# CristmasVillage_Driver_1-3.net
KiCad netlist of a schematic drawn in EAGLE
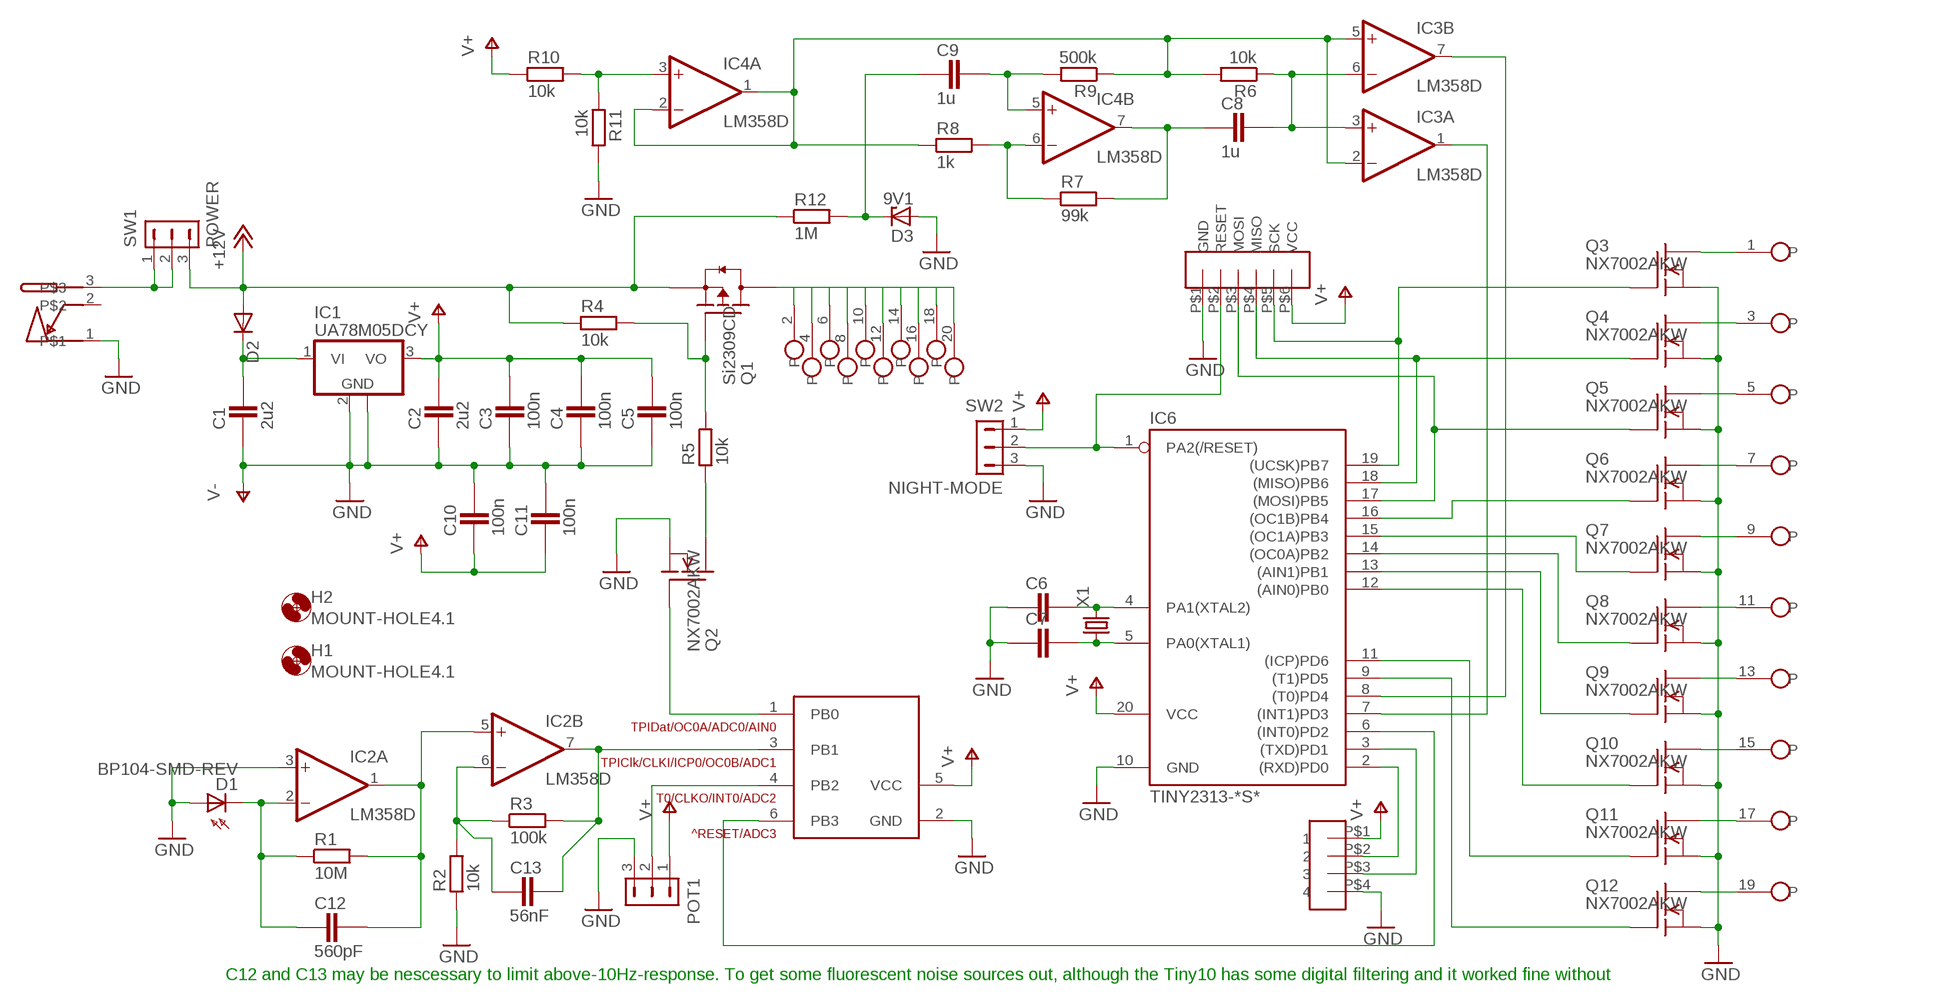
[diagram p0: schematic, sheet 1]

(export (version "E")
  (design (tool "Eeschema 10.0.6"))
  (components
    (comp (ref "C1")
      (value "2u2")
      (footprint "eagle-import:CAPC3215X168N")
      (libsource (lib "eagle-import") (part "CAPACITOR_1206"))
    )
    (comp (ref "C2")
      (value "2u2")
      (footprint "eagle-import:CAPC3215X168N")
      (libsource (lib "eagle-import") (part "CAPACITOR_1206"))
    )
    (comp (ref "C3")
      (value "100n")
      (footprint "eagle-import:CAPC1608X92N")
      (libsource (lib "eagle-import") (part "CAPACITOR_0603"))
    )
    (comp (ref "C4")
      (value "100n")
      (footprint "eagle-import:CAPC1608X92N")
      (libsource (lib "eagle-import") (part "CAPACITOR_0603"))
    )
    (comp (ref "C5")
      (value "100n")
      (footprint "eagle-import:CAPC1608X92N")
      (libsource (lib "eagle-import") (part "CAPACITOR_0603"))
    )
    (comp (ref "C6")
      (value "CAPACITOR_0603")
      (footprint "eagle-import:CAPC1608X92N")
      (libsource (lib "eagle-import") (part "CAPACITOR_0603"))
    )
    (comp (ref "C7")
      (value "CAPACITOR_0603")
      (footprint "eagle-import:CAPC1608X92N")
      (libsource (lib "eagle-import") (part "CAPACITOR_0603"))
    )
    (comp (ref "C8")
      (value "1u")
      (footprint "eagle-import:CAPC3215X168N")
      (libsource (lib "eagle-import") (part "CAPACITOR_1206"))
    )
    (comp (ref "C9")
      (value "1u")
      (footprint "eagle-import:CAPC3215X168N")
      (libsource (lib "eagle-import") (part "CAPACITOR_1206"))
    )
    (comp (ref "C10")
      (value "100n")
      (footprint "eagle-import:CAPC1608X92N")
      (libsource (lib "eagle-import") (part "CAPACITOR_0603"))
    )
    (comp (ref "C11")
      (value "100n")
      (footprint "eagle-import:CAPC1608X92N")
      (libsource (lib "eagle-import") (part "CAPACITOR_0603"))
    )
    (comp (ref "C12")
      (value "560pF")
      (footprint "eagle-import:CAPC1608X92N")
      (libsource (lib "eagle-import") (part "CAPACITOR_0603"))
    )
    (comp (ref "C13")
      (value "56nF")
      (footprint "eagle-import:CAPC1608X92N")
      (libsource (lib "eagle-import") (part "CAPACITOR_0603"))
    )
    (comp (ref "CN1")
      (value "MJ-180SMT")
      (footprint "eagle-import:MJ-180SMT")
      (libsource (lib "eagle-import") (part "MJ-180SMT"))
    )
    (comp (ref "CN2-PROG")
      (value "JST-6PSPI-SIDE-S6B")
      (footprint "eagle-import:6P-H")
      (libsource (lib "eagle-import") (part "JST-6PSPI-SIDE-S6B"))
    )
    (comp (ref "CN3-SERIAL")
      (value "JST-4PSIDE-S4B")
      (footprint "eagle-import:4P-H")
      (libsource (lib "eagle-import") (part "JST-4PSIDE-S4B"))
    )
    (comp (ref "CN5-LEDSTRIPS")
      (value "HDR_2X10_SIDE-MOUNT")
      (footprint "eagle-import:20PIN-10TOP-10BOT")
      (libsource (lib "eagle-import") (part "HDR_2X10_SIDE-MOUNT"))
    )
    (comp (ref "D1")
      (value "BP104-SMD-REV")
      (footprint "eagle-import:BR104SMDREV")
      (libsource (lib "eagle-import") (part "BP104-SMD-REV"))
    )
    (comp (ref "D2")
      (value "DIODE-MINIMELF")
      (footprint "eagle-import:MINIMELF")
      (libsource (lib "eagle-import") (part "DIODE-MINIMELF"))
    )
    (comp (ref "D3")
      (value "9V1")
      (footprint "eagle-import:SOT23")
      (libsource (lib "eagle-import") (part "ZENER-DIODESOT23"))
    )
    (comp (ref "H1")
      (value "MOUNT-HOLE4.1")
      (footprint "eagle-import:4,1")
      (libsource (lib "eagle-import") (part "MOUNT-HOLE4.1"))
    )
    (comp (ref "H2")
      (value "MOUNT-HOLE4.1")
      (footprint "eagle-import:4,1")
      (libsource (lib "eagle-import") (part "MOUNT-HOLE4.1"))
    )
    (comp (ref "IC1")
      (value "UA78M05DCY")
      (footprint "eagle-import:SOT223")
      (libsource (lib "eagle-import") (part "UA78MDCY05"))
    )
    (comp (ref "IC2")
      (value "LM358D")
      (footprint "eagle-import:SO08")
      (libsource (lib "eagle-import") (part "LM358D"))
    )
    (comp (ref "IC3")
      (value "LM358D")
      (footprint "eagle-import:SO08")
      (libsource (lib "eagle-import") (part "LM358D"))
    )
    (comp (ref "IC4")
      (value "LM358D")
      (footprint "eagle-import:SO08")
      (libsource (lib "eagle-import") (part "LM358D"))
    )
    (comp (ref "IC5")
      (value "ATTINY-4/5/9/10")
      (footprint "eagle-import:SOT23-6")
      (libsource (lib "eagle-import") (part "ATTINY-4/5/9/10"))
    )
    (comp (ref "IC6")
      (value "TINY2313-*S*")
      (footprint "eagle-import:SO20L$")
      (libsource (lib "eagle-import") (part "TINY2313-S"))
    )
    (comp (ref "POT1")
      (value "HDR-1X3-MTE-100")
      (footprint "eagle-import:MTE-100-3V")
      (libsource (lib "eagle-import") (part "HDR-1X3-MTE-100"))
    )
    (comp (ref "Q1")
      (value "Si2309CD")
      (footprint "eagle-import:SOT95P280X135-3N")
      (libsource (lib "eagle-import") (part "MOSFET-PCH_SOT-23"))
    )
    (comp (ref "Q2")
      (value "NX7002AKW")
      (footprint "eagle-import:SOT323R")
      (libsource (lib "eagle-import") (part "NX7002AKW"))
    )
    (comp (ref "Q3")
      (value "NX7002AKW")
      (footprint "eagle-import:SOT323R")
      (libsource (lib "eagle-import") (part "NX7002AKW"))
    )
    (comp (ref "Q4")
      (value "NX7002AKW")
      (footprint "eagle-import:SOT323R")
      (libsource (lib "eagle-import") (part "NX7002AKW"))
    )
    (comp (ref "Q5")
      (value "NX7002AKW")
      (footprint "eagle-import:SOT323R")
      (libsource (lib "eagle-import") (part "NX7002AKW"))
    )
    (comp (ref "Q6")
      (value "NX7002AKW")
      (footprint "eagle-import:SOT323R")
      (libsource (lib "eagle-import") (part "NX7002AKW"))
    )
    (comp (ref "Q7")
      (value "NX7002AKW")
      (footprint "eagle-import:SOT323R")
      (libsource (lib "eagle-import") (part "NX7002AKW"))
    )
    (comp (ref "Q8")
      (value "NX7002AKW")
      (footprint "eagle-import:SOT323R")
      (libsource (lib "eagle-import") (part "NX7002AKW"))
    )
    (comp (ref "Q9")
      (value "NX7002AKW")
      (footprint "eagle-import:SOT323R")
      (libsource (lib "eagle-import") (part "NX7002AKW"))
    )
    (comp (ref "Q10")
      (value "NX7002AKW")
      (footprint "eagle-import:SOT323R")
      (libsource (lib "eagle-import") (part "NX7002AKW"))
    )
    (comp (ref "Q11")
      (value "NX7002AKW")
      (footprint "eagle-import:SOT323R")
      (libsource (lib "eagle-import") (part "NX7002AKW"))
    )
    (comp (ref "Q12")
      (value "NX7002AKW")
      (footprint "eagle-import:SOT323R")
      (libsource (lib "eagle-import") (part "NX7002AKW"))
    )
    (comp (ref "R1")
      (value "10M")
      (footprint "eagle-import:RESC1608X55N")
      (libsource (lib "eagle-import") (part "RESISTOR_0603"))
    )
    (comp (ref "R2")
      (value "10k")
      (footprint "eagle-import:RESC1608X55N")
      (libsource (lib "eagle-import") (part "RESISTOR_0603"))
    )
    (comp (ref "R3")
      (value "100k")
      (footprint "eagle-import:RESC1608X55N")
      (libsource (lib "eagle-import") (part "RESISTOR_0603"))
    )
    (comp (ref "R4")
      (value "10k")
      (footprint "eagle-import:RESC1608X55N")
      (libsource (lib "eagle-import") (part "RESISTOR_0603"))
    )
    (comp (ref "R5")
      (value "10k")
      (footprint "eagle-import:RESC1608X55N")
      (libsource (lib "eagle-import") (part "RESISTOR_0603"))
    )
    (comp (ref "R6")
      (value "10k")
      (footprint "eagle-import:RESC1608X55N")
      (libsource (lib "eagle-import") (part "RESISTOR_0603"))
    )
    (comp (ref "R7")
      (value "99k")
      (footprint "eagle-import:RESC1608X55N")
      (libsource (lib "eagle-import") (part "RESISTOR_0603"))
    )
    (comp (ref "R8")
      (value "1k")
      (footprint "eagle-import:RESC1608X55N")
      (libsource (lib "eagle-import") (part "RESISTOR_0603"))
    )
    (comp (ref "R9")
      (value "500k")
      (footprint "eagle-import:RESC1608X55N")
      (libsource (lib "eagle-import") (part "RESISTOR_0603"))
    )
    (comp (ref "R10")
      (value "10k")
      (footprint "eagle-import:RESC1608X55N")
      (libsource (lib "eagle-import") (part "RESISTOR_0603"))
    )
    (comp (ref "R11")
      (value "10k")
      (footprint "eagle-import:RESC1608X55N")
      (libsource (lib "eagle-import") (part "RESISTOR_0603"))
    )
    (comp (ref "R12")
      (value "1M")
      (footprint "eagle-import:RESC1608X55N")
      (libsource (lib "eagle-import") (part "RESISTOR_0603"))
    )
    (comp (ref "SW1")
      (value "POWER")
      (footprint "eagle-import:MTE-100-3V")
      (libsource (lib "eagle-import") (part "HDR-1X3-MTE-100"))
    )
    (comp (ref "SW2")
      (value "NIGHT-MODE")
      (footprint "eagle-import:MTE-100-3V")
      (libsource (lib "eagle-import") (part "HDR-1X3-MTE-100"))
    )
    (comp (ref "X1")
      (value "CRYSTALSM49")
      (footprint "eagle-import:SM49")
      (libsource (lib "eagle-import") (part "CRYSTALSM49"))
    )
  )
  (nets
    (net (code "1") (name "+12V") (class "Default")
      (node (ref "D2") (pin "A") (pinfunction "A_A") (pintype "passive"))
      (node (ref "Q1") (pin "2") (pinfunction "S_2") (pintype "passive"))
      (node (ref "R12") (pin "1") (pinfunction "1_1") (pintype "passive"))
      (node (ref "R4") (pin "1") (pinfunction "1_1") (pintype "passive"))
      (node (ref "SW1") (pin "3") (pinfunction "3_3") (pintype "passive"))
    )
    (net (code "2") (name "GND") (class "Default")
      (node (ref "C1") (pin "1") (pinfunction "1_1") (pintype "passive"))
      (node (ref "C10") (pin "2") (pinfunction "2_2") (pintype "passive"))
      (node (ref "C11") (pin "2") (pinfunction "2_2") (pintype "passive"))
      (node (ref "C2") (pin "1") (pinfunction "1_1") (pintype "passive"))
      (node (ref "C3") (pin "1") (pinfunction "1_1") (pintype "passive"))
      (node (ref "C4") (pin "1") (pinfunction "1_1") (pintype "passive"))
      (node (ref "C5") (pin "1") (pinfunction "1_1") (pintype "passive"))
      (node (ref "C6") (pin "1") (pinfunction "1_1") (pintype "passive"))
      (node (ref "C7") (pin "1") (pinfunction "1_1") (pintype "passive"))
      (node (ref "CN1") (pin "1") (pinfunction "P$1_1") (pintype "bidirectional"))
      (node (ref "CN2-PROG") (pin "P$1") (pinfunction "GND_P$1") (pintype "bidirectional"))
      (node (ref "CN3-SERIAL") (pin "P$4") (pinfunction "4_P$4") (pintype "bidirectional"))
      (node (ref "D1") (pin "1") (pinfunction "A_1") (pintype "passive"))
      (node (ref "D3") (pin "1") (pinfunction "A_1") (pintype "passive"))
      (node (ref "IC1") (pin "2") (pinfunction "GND_2") (pintype "passive"))
      (node (ref "IC1") (pin "4") (pinfunction "GND_4") (pintype "passive"))
      (node (ref "IC2") (pin "3") (pinfunction "+IN_3") (pintype "input"))
      (node (ref "IC5") (pin "2") (pinfunction "GND_2") (pintype "bidirectional"))
      (node (ref "IC6") (pin "10") (pinfunction "GND_10") (pintype "power_in"))
      (node (ref "POT1") (pin "3") (pinfunction "3_3") (pintype "passive"))
      (node (ref "Q10") (pin "2") (pinfunction "S_2") (pintype "passive"))
      (node (ref "Q11") (pin "2") (pinfunction "S_2") (pintype "passive"))
      (node (ref "Q12") (pin "2") (pinfunction "S_2") (pintype "passive"))
      (node (ref "Q2") (pin "2") (pinfunction "S_2") (pintype "passive"))
      (node (ref "Q3") (pin "2") (pinfunction "S_2") (pintype "passive"))
      (node (ref "Q4") (pin "2") (pinfunction "S_2") (pintype "passive"))
      (node (ref "Q5") (pin "2") (pinfunction "S_2") (pintype "passive"))
      (node (ref "Q6") (pin "2") (pinfunction "S_2") (pintype "passive"))
      (node (ref "Q7") (pin "2") (pinfunction "S_2") (pintype "passive"))
      (node (ref "Q8") (pin "2") (pinfunction "S_2") (pintype "passive"))
      (node (ref "Q9") (pin "2") (pinfunction "S_2") (pintype "passive"))
      (node (ref "R11") (pin "2") (pinfunction "2_2") (pintype "passive"))
      (node (ref "R2") (pin "1") (pinfunction "1_1") (pintype "passive"))
      (node (ref "SW2") (pin "3") (pinfunction "3_3") (pintype "passive"))
    )
    (net (code "3") (name "Net-(CN1-P$3)") (class "Default")
      (node (ref "CN1") (pin "3") (pinfunction "P$3_3") (pintype "bidirectional"))
      (node (ref "SW1") (pin "1") (pinfunction "1_1") (pintype "passive"))
      (node (ref "SW1") (pin "2") (pinfunction "2_2") (pintype "passive"))
    )
    (net (code "4") (name "Net-(CN2-PROG-MISO)") (class "Default")
      (node (ref "CN2-PROG") (pin "P$4") (pinfunction "MISO_P$4") (pintype "bidirectional"))
      (node (ref "IC6") (pin "18") (pinfunction "(MISO)PB6_18") (pintype "bidirectional"))
      (node (ref "Q4") (pin "1") (pinfunction "G_1") (pintype "passive"))
    )
    (net (code "5") (name "Net-(CN2-PROG-MOSI)") (class "Default")
      (node (ref "CN2-PROG") (pin "P$3") (pinfunction "MOSI_P$3") (pintype "bidirectional"))
      (node (ref "IC6") (pin "17") (pinfunction "(MOSI)PB5_17") (pintype "bidirectional"))
      (node (ref "Q5") (pin "1") (pinfunction "G_1") (pintype "passive"))
    )
    (net (code "6") (name "Net-(CN2-PROG-RESET)") (class "Default")
      (node (ref "CN2-PROG") (pin "P$2") (pinfunction "RESET_P$2") (pintype "bidirectional"))
      (node (ref "IC6") (pin "1") (pinfunction "PA2(/RESET)_1") (pintype "input"))
      (node (ref "SW2") (pin "2") (pinfunction "2_2") (pintype "passive"))
    )
    (net (code "7") (name "Net-(CN2-PROG-SCK)") (class "Default")
      (node (ref "CN2-PROG") (pin "P$5") (pinfunction "SCK_P$5") (pintype "bidirectional"))
      (node (ref "IC6") (pin "19") (pinfunction "(UCSK)PB7_19") (pintype "bidirectional"))
      (node (ref "Q3") (pin "1") (pinfunction "G_1") (pintype "passive"))
    )
    (net (code "8") (name "Net-(CN3-SERIAL-2)") (class "Default")
      (node (ref "CN3-SERIAL") (pin "P$2") (pinfunction "2_P$2") (pintype "bidirectional"))
      (node (ref "IC6") (pin "2") (pinfunction "(RXD)PD0_2") (pintype "bidirectional"))
    )
    (net (code "9") (name "Net-(CN3-SERIAL-3)") (class "Default")
      (node (ref "CN3-SERIAL") (pin "P$3") (pinfunction "3_P$3") (pintype "bidirectional"))
      (node (ref "IC6") (pin "3") (pinfunction "(TXD)PD1_3") (pintype "bidirectional"))
    )
    (net (code "10") (name "Net-(CN5-LEDSTRIPSA-P)") (class "Default")
      (node (ref "CN5-LEDSTRIPS") (pin "1") (pinfunction "P_1") (pintype "bidirectional"))
      (node (ref "Q3") (pin "3") (pinfunction "D_3") (pintype "passive"))
    )
    (net (code "11") (name "Net-(CN5-LEDSTRIPSB-P)") (class "Default")
      (node (ref "CN5-LEDSTRIPS") (pin "10") (pinfunction "P_10") (pintype "bidirectional"))
      (node (ref "CN5-LEDSTRIPS") (pin "12") (pinfunction "P_12") (pintype "bidirectional"))
      (node (ref "CN5-LEDSTRIPS") (pin "14") (pinfunction "P_14") (pintype "bidirectional"))
      (node (ref "CN5-LEDSTRIPS") (pin "16") (pinfunction "P_16") (pintype "bidirectional"))
      (node (ref "CN5-LEDSTRIPS") (pin "18") (pinfunction "P_18") (pintype "bidirectional"))
      (node (ref "CN5-LEDSTRIPS") (pin "2") (pinfunction "P_2") (pintype "bidirectional"))
      (node (ref "CN5-LEDSTRIPS") (pin "20") (pinfunction "P_20") (pintype "bidirectional"))
      (node (ref "CN5-LEDSTRIPS") (pin "4") (pinfunction "P_4") (pintype "bidirectional"))
      (node (ref "CN5-LEDSTRIPS") (pin "6") (pinfunction "P_6") (pintype "bidirectional"))
      (node (ref "CN5-LEDSTRIPS") (pin "8") (pinfunction "P_8") (pintype "bidirectional"))
      (node (ref "Q1") (pin "3") (pinfunction "D_3") (pintype "passive"))
    )
    (net (code "12") (name "Net-(CN5-LEDSTRIPSC-P)") (class "Default")
      (node (ref "CN5-LEDSTRIPS") (pin "11") (pinfunction "P_11") (pintype "bidirectional"))
      (node (ref "Q8") (pin "3") (pinfunction "D_3") (pintype "passive"))
    )
    (net (code "13") (name "Net-(CN5-LEDSTRIPSE-P)") (class "Default")
      (node (ref "CN5-LEDSTRIPS") (pin "13") (pinfunction "P_13") (pintype "bidirectional"))
      (node (ref "Q9") (pin "3") (pinfunction "D_3") (pintype "passive"))
    )
    (net (code "14") (name "Net-(CN5-LEDSTRIPSG-P)") (class "Default")
      (node (ref "CN5-LEDSTRIPS") (pin "15") (pinfunction "P_15") (pintype "bidirectional"))
      (node (ref "Q10") (pin "3") (pinfunction "D_3") (pintype "passive"))
    )
    (net (code "15") (name "Net-(CN5-LEDSTRIPSI-P)") (class "Default")
      (node (ref "CN5-LEDSTRIPS") (pin "17") (pinfunction "P_17") (pintype "bidirectional"))
      (node (ref "Q11") (pin "3") (pinfunction "D_3") (pintype "passive"))
    )
    (net (code "16") (name "Net-(CN5-LEDSTRIPSK-P)") (class "Default")
      (node (ref "CN5-LEDSTRIPS") (pin "19") (pinfunction "P_19") (pintype "bidirectional"))
      (node (ref "Q12") (pin "3") (pinfunction "D_3") (pintype "passive"))
    )
    (net (code "17") (name "Net-(CN5-LEDSTRIPSN-P)") (class "Default")
      (node (ref "CN5-LEDSTRIPS") (pin "3") (pinfunction "P_3") (pintype "bidirectional"))
      (node (ref "Q4") (pin "3") (pinfunction "D_3") (pintype "passive"))
    )
    (net (code "18") (name "Net-(CN5-LEDSTRIPSP-P)") (class "Default")
      (node (ref "CN5-LEDSTRIPS") (pin "5") (pinfunction "P_5") (pintype "bidirectional"))
      (node (ref "Q5") (pin "3") (pinfunction "D_3") (pintype "passive"))
    )
    (net (code "19") (name "Net-(CN5-LEDSTRIPSR-P)") (class "Default")
      (node (ref "CN5-LEDSTRIPS") (pin "7") (pinfunction "P_7") (pintype "bidirectional"))
      (node (ref "Q6") (pin "3") (pinfunction "D_3") (pintype "passive"))
    )
    (net (code "20") (name "Net-(CN5-LEDSTRIPST-P)") (class "Default")
      (node (ref "CN5-LEDSTRIPS") (pin "9") (pinfunction "P_9") (pintype "bidirectional"))
      (node (ref "Q7") (pin "3") (pinfunction "D_3") (pintype "passive"))
    )
    (net (code "21") (name "Net-(D1-C)") (class "Default")
      (node (ref "C12") (pin "1") (pinfunction "1_1") (pintype "passive"))
      (node (ref "D1") (pin "2") (pinfunction "C_2") (pintype "passive"))
      (node (ref "IC2") (pin "2") (pinfunction "-IN_2") (pintype "input"))
      (node (ref "R1") (pin "1") (pinfunction "1_1") (pintype "passive"))
    )
    (net (code "22") (name "Net-(D3-C)") (class "Default")
      (node (ref "C9") (pin "1") (pinfunction "1_1") (pintype "passive"))
      (node (ref "D3") (pin "3") (pinfunction "C_3") (pintype "passive"))
      (node (ref "R12") (pin "2") (pinfunction "2_2") (pintype "passive"))
    )
    (net (code "23") (name "Net-(IC1-VI)") (class "Default")
      (node (ref "C1") (pin "2") (pinfunction "2_2") (pintype "passive"))
      (node (ref "D2") (pin "C") (pinfunction "C_C") (pintype "passive"))
      (node (ref "IC1") (pin "1") (pinfunction "VI_1") (pintype "input"))
    )
    (net (code "24") (name "Net-(IC2A-OUT)") (class "Default")
      (node (ref "C12") (pin "2") (pinfunction "2_2") (pintype "passive"))
      (node (ref "IC2") (pin "1") (pinfunction "OUT_1") (pintype "output"))
      (node (ref "IC2") (pin "5") (pinfunction "+IN_5") (pintype "input"))
      (node (ref "R1") (pin "2") (pinfunction "2_2") (pintype "passive"))
    )
    (net (code "25") (name "Net-(IC2B--IN)") (class "Default")
      (node (ref "C13") (pin "1") (pinfunction "1_1") (pintype "passive"))
      (node (ref "IC2") (pin "6") (pinfunction "-IN_6") (pintype "input"))
      (node (ref "R2") (pin "2") (pinfunction "2_2") (pintype "passive"))
      (node (ref "R3") (pin "1") (pinfunction "1_1") (pintype "passive"))
    )
    (net (code "26") (name "Net-(IC2B-OUT)") (class "Default")
      (node (ref "C13") (pin "2") (pinfunction "2_2") (pintype "passive"))
      (node (ref "IC2") (pin "7") (pinfunction "OUT_7") (pintype "output"))
      (node (ref "IC5") (pin "3") (pinfunction "PB1_3") (pintype "bidirectional"))
      (node (ref "R3") (pin "2") (pinfunction "2_2") (pintype "passive"))
    )
    (net (code "27") (name "Net-(IC3A-+IN)") (class "Default")
      (node (ref "C8") (pin "2") (pinfunction "2_2") (pintype "passive"))
      (node (ref "IC3") (pin "3") (pinfunction "+IN_3") (pintype "input"))
      (node (ref "IC3") (pin "6") (pinfunction "-IN_6") (pintype "input"))
      (node (ref "R6") (pin "1") (pinfunction "1_1") (pintype "passive"))
    )
    (net (code "28") (name "Net-(IC3A--IN)") (class "Default")
      (node (ref "IC3") (pin "2") (pinfunction "-IN_2") (pintype "input"))
      (node (ref "IC3") (pin "5") (pinfunction "+IN_5") (pintype "input"))
      (node (ref "IC4") (pin "1") (pinfunction "OUT_1") (pintype "output"))
      (node (ref "IC4") (pin "2") (pinfunction "-IN_2") (pintype "input"))
      (node (ref "R6") (pin "2") (pinfunction "2_2") (pintype "passive"))
      (node (ref "R8") (pin "1") (pinfunction "1_1") (pintype "passive"))
      (node (ref "R9") (pin "1") (pinfunction "1_1") (pintype "passive"))
    )
    (net (code "29") (name "Net-(IC3A-OUT)") (class "Default")
      (node (ref "IC3") (pin "1") (pinfunction "OUT_1") (pintype "output"))
      (node (ref "IC6") (pin "7") (pinfunction "(INT1)PD3_7") (pintype "bidirectional"))
    )
    (net (code "30") (name "Net-(IC3B-OUT)") (class "Default")
      (node (ref "IC3") (pin "7") (pinfunction "OUT_7") (pintype "output"))
      (node (ref "IC6") (pin "8") (pinfunction "(T0)PD4_8") (pintype "bidirectional"))
    )
    (net (code "31") (name "Net-(IC4A-+IN)") (class "Default")
      (node (ref "IC4") (pin "3") (pinfunction "+IN_3") (pintype "input"))
      (node (ref "R10") (pin "2") (pinfunction "2_2") (pintype "passive"))
      (node (ref "R11") (pin "1") (pinfunction "1_1") (pintype "passive"))
    )
    (net (code "32") (name "Net-(IC4B-+IN)") (class "Default")
      (node (ref "C9") (pin "2") (pinfunction "2_2") (pintype "passive"))
      (node (ref "IC4") (pin "5") (pinfunction "+IN_5") (pintype "input"))
      (node (ref "R9") (pin "2") (pinfunction "2_2") (pintype "passive"))
    )
    (net (code "33") (name "Net-(IC4B--IN)") (class "Default")
      (node (ref "IC4") (pin "6") (pinfunction "-IN_6") (pintype "input"))
      (node (ref "R7") (pin "1") (pinfunction "1_1") (pintype "passive"))
      (node (ref "R8") (pin "2") (pinfunction "2_2") (pintype "passive"))
    )
    (net (code "34") (name "Net-(IC4B-OUT)") (class "Default")
      (node (ref "C8") (pin "1") (pinfunction "1_1") (pintype "passive"))
      (node (ref "IC4") (pin "7") (pinfunction "OUT_7") (pintype "output"))
      (node (ref "R7") (pin "2") (pinfunction "2_2") (pintype "passive"))
    )
    (net (code "35") (name "Net-(IC5-PB0)") (class "Default")
      (node (ref "IC5") (pin "1") (pinfunction "PB0_1") (pintype "bidirectional"))
      (node (ref "Q2") (pin "1") (pinfunction "G_1") (pintype "passive"))
    )
    (net (code "36") (name "Net-(IC5-PB2)") (class "Default")
      (node (ref "IC5") (pin "4") (pinfunction "PB2_4") (pintype "bidirectional"))
      (node (ref "POT1") (pin "2") (pinfunction "2_2") (pintype "passive"))
    )
    (net (code "37") (name "Net-(IC5-PB3)") (class "Default")
      (node (ref "IC5") (pin "6") (pinfunction "PB3_6") (pintype "bidirectional"))
      (node (ref "IC6") (pin "6") (pinfunction "(INT0)PD2_6") (pintype "bidirectional"))
    )
    (net (code "38") (name "Net-(IC6-(AIN0)PB0)") (class "Default")
      (node (ref "IC6") (pin "12") (pinfunction "(AIN0)PB0_12") (pintype "bidirectional"))
      (node (ref "Q10") (pin "1") (pinfunction "G_1") (pintype "passive"))
    )
    (net (code "39") (name "Net-(IC6-(AIN1)PB1)") (class "Default")
      (node (ref "IC6") (pin "13") (pinfunction "(AIN1)PB1_13") (pintype "bidirectional"))
      (node (ref "Q9") (pin "1") (pinfunction "G_1") (pintype "passive"))
    )
    (net (code "40") (name "Net-(IC6-(ICP)PD6)") (class "Default")
      (node (ref "IC6") (pin "11") (pinfunction "(ICP)PD6_11") (pintype "bidirectional"))
      (node (ref "Q11") (pin "1") (pinfunction "G_1") (pintype "passive"))
    )
    (net (code "41") (name "Net-(IC6-(OC0A)PB2)") (class "Default")
      (node (ref "IC6") (pin "14") (pinfunction "(OC0A)PB2_14") (pintype "bidirectional"))
      (node (ref "Q8") (pin "1") (pinfunction "G_1") (pintype "passive"))
    )
    (net (code "42") (name "Net-(IC6-(OC1A)PB3)") (class "Default")
      (node (ref "IC6") (pin "15") (pinfunction "(OC1A)PB3_15") (pintype "bidirectional"))
      (node (ref "Q7") (pin "1") (pinfunction "G_1") (pintype "passive"))
    )
    (net (code "43") (name "Net-(IC6-(OC1B)PB4)") (class "Default")
      (node (ref "IC6") (pin "16") (pinfunction "(OC1B)PB4_16") (pintype "bidirectional"))
      (node (ref "Q6") (pin "1") (pinfunction "G_1") (pintype "passive"))
    )
    (net (code "44") (name "Net-(IC6-(T1)PD5)") (class "Default")
      (node (ref "IC6") (pin "9") (pinfunction "(T1)PD5_9") (pintype "bidirectional"))
      (node (ref "Q12") (pin "1") (pinfunction "G_1") (pintype "passive"))
    )
    (net (code "45") (name "Net-(IC6-PA0(XTAL1))") (class "Default")
      (node (ref "C7") (pin "2") (pinfunction "2_2") (pintype "passive"))
      (node (ref "IC6") (pin "5") (pinfunction "PA0(XTAL1)_5") (pintype "bidirectional"))
      (node (ref "X1") (pin "1") (pinfunction "1_1") (pintype "passive"))
    )
    (net (code "46") (name "Net-(IC6-PA1(XTAL2))") (class "Default")
      (node (ref "C6") (pin "2") (pinfunction "2_2") (pintype "passive"))
      (node (ref "IC6") (pin "4") (pinfunction "PA1(XTAL2)_4") (pintype "bidirectional"))
      (node (ref "X1") (pin "2") (pinfunction "2_2") (pintype "passive"))
    )
    (net (code "47") (name "Net-(Q1-G)") (class "Default")
      (node (ref "Q1") (pin "1") (pinfunction "G_1") (pintype "passive"))
      (node (ref "R4") (pin "2") (pinfunction "2_2") (pintype "passive"))
      (node (ref "R5") (pin "2") (pinfunction "2_2") (pintype "passive"))
    )
    (net (code "48") (name "Net-(Q2-D)") (class "Default")
      (node (ref "Q2") (pin "3") (pinfunction "D_3") (pintype "passive"))
      (node (ref "R5") (pin "1") (pinfunction "1_1") (pintype "passive"))
    )
    (net (code "49") (name "V+") (class "Default")
      (node (ref "C10") (pin "1") (pinfunction "1_1") (pintype "passive"))
      (node (ref "C11") (pin "1") (pinfunction "1_1") (pintype "passive"))
      (node (ref "C2") (pin "2") (pinfunction "2_2") (pintype "passive"))
      (node (ref "C3") (pin "2") (pinfunction "2_2") (pintype "passive"))
      (node (ref "C4") (pin "2") (pinfunction "2_2") (pintype "passive"))
      (node (ref "C5") (pin "2") (pinfunction "2_2") (pintype "passive"))
      (node (ref "CN2-PROG") (pin "P$6") (pinfunction "VCC_P$6") (pintype "bidirectional"))
      (node (ref "CN3-SERIAL") (pin "P$1") (pinfunction "1_P$1") (pintype "bidirectional"))
      (node (ref "IC1") (pin "3") (pinfunction "VO_3") (pintype "passive"))
      (node (ref "IC5") (pin "5") (pinfunction "VCC_5") (pintype "bidirectional"))
      (node (ref "IC6") (pin "20") (pinfunction "VCC_20") (pintype "power_in"))
      (node (ref "POT1") (pin "1") (pinfunction "1_1") (pintype "passive"))
      (node (ref "R10") (pin "1") (pinfunction "1_1") (pintype "passive"))
      (node (ref "SW2") (pin "1") (pinfunction "1_1") (pintype "passive"))
    )
    (net (code "50") (name "unconnected-(CN1-P$2-Pad2)") (class "Default")
      (node (ref "CN1") (pin "2") (pinfunction "P$2_2") (pintype "bidirectional"))
    )
  )
)
